# heater-LC-filtering.net
KiCad netlist of a schematic drawn in Altium Designer
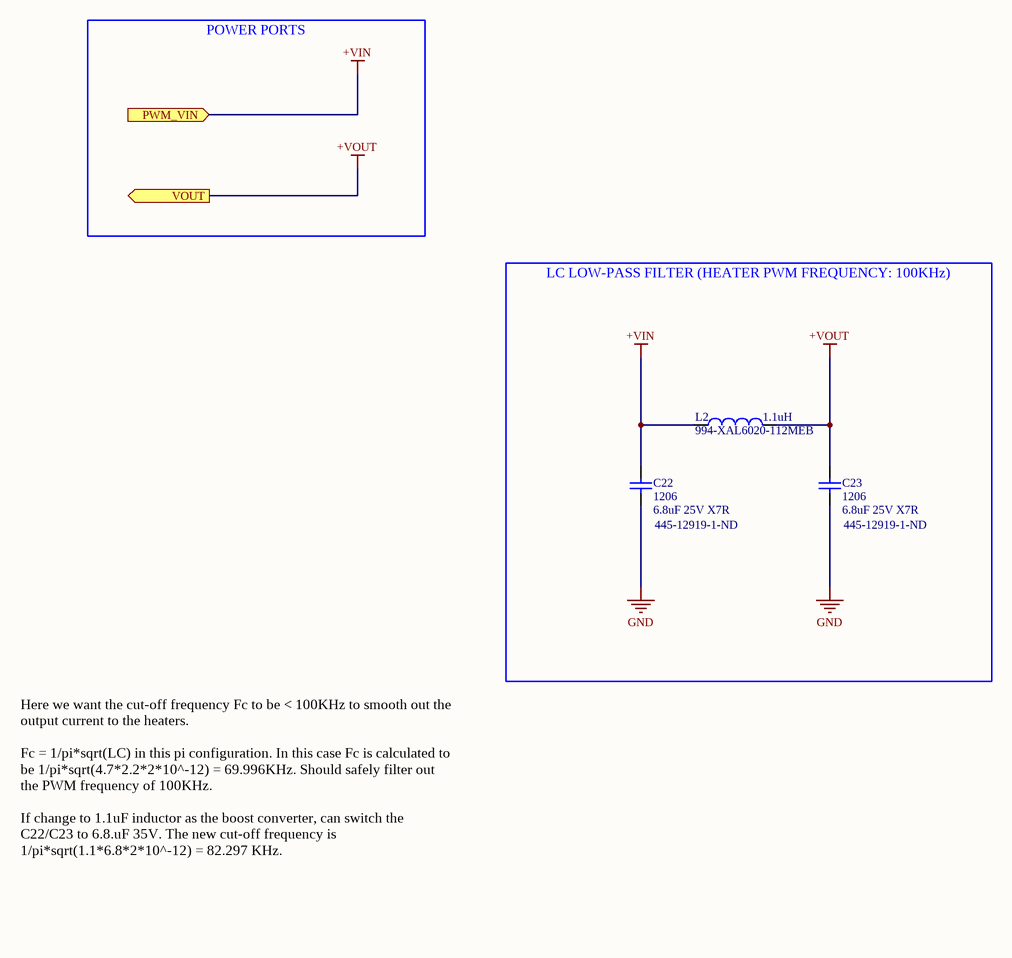
[diagram p0: heater-LC-filtering.SchDoc]

(export (version "E")
  (design (tool "Eeschema 10.0.6"))
  (components
    (comp (ref "C22")
      (value "1206")
      (footprint "CAP1206R")
      (description "1206 capacitor")
      (fields
        (field (name "ALTIUM_VALUE") "6.8uF 25V X7R")
        (field (name "SUPPLIER PART NUMBER 1") "445-12919-1-ND")
      )
      (libsource (lib "CAP1206") (part "CAP1206"))
    )
    (comp (ref "C23")
      (value "1206")
      (footprint "CAP1206R")
      (description "1206 capacitor")
      (fields
        (field (name "ALTIUM_VALUE") "6.8uF 25V X7R")
        (field (name "SUPPLIER PART NUMBER 1") "445-12919-1-ND")
      )
      (libsource (lib "CAP1206") (part "CAP1206"))
    )
    (comp (ref "L2")
      (value "1.1uH")
      (footprint "XAL6030-122")
      (description "Inductor")
      (fields
        (field (name "SUPPLIER PART NUMBER 1") "994-XAL6020-112MEB")
        (field (name "PUBLISHER") "Altium Limited")
      )
      (libsource (lib "Miscellaneous Devices") (part "Inductor"))
    )
  )
  (nets
    (net (code "1") (name "+VIN") (class "Default")
      (node (ref "C22") (pin "2") (pinfunction "2_2") (pintype "passive"))
      (node (ref "L2") (pin "1") (pinfunction "1_1") (pintype "passive"))
    )
    (net (code "2") (name "+VOUT") (class "Default")
      (node (ref "C23") (pin "2") (pinfunction "2_2") (pintype "passive"))
      (node (ref "L2") (pin "2") (pinfunction "2_2") (pintype "passive"))
    )
    (net (code "3") (name "GND") (class "Default")
      (node (ref "C22") (pin "1") (pinfunction "1_1") (pintype "passive"))
      (node (ref "C23") (pin "1") (pinfunction "1_1") (pintype "passive"))
    )
  )
)
